# SCH_USB2MULTIRS_2022-08-20.net
KiCad netlist of a schematic drawn in EasyEDA
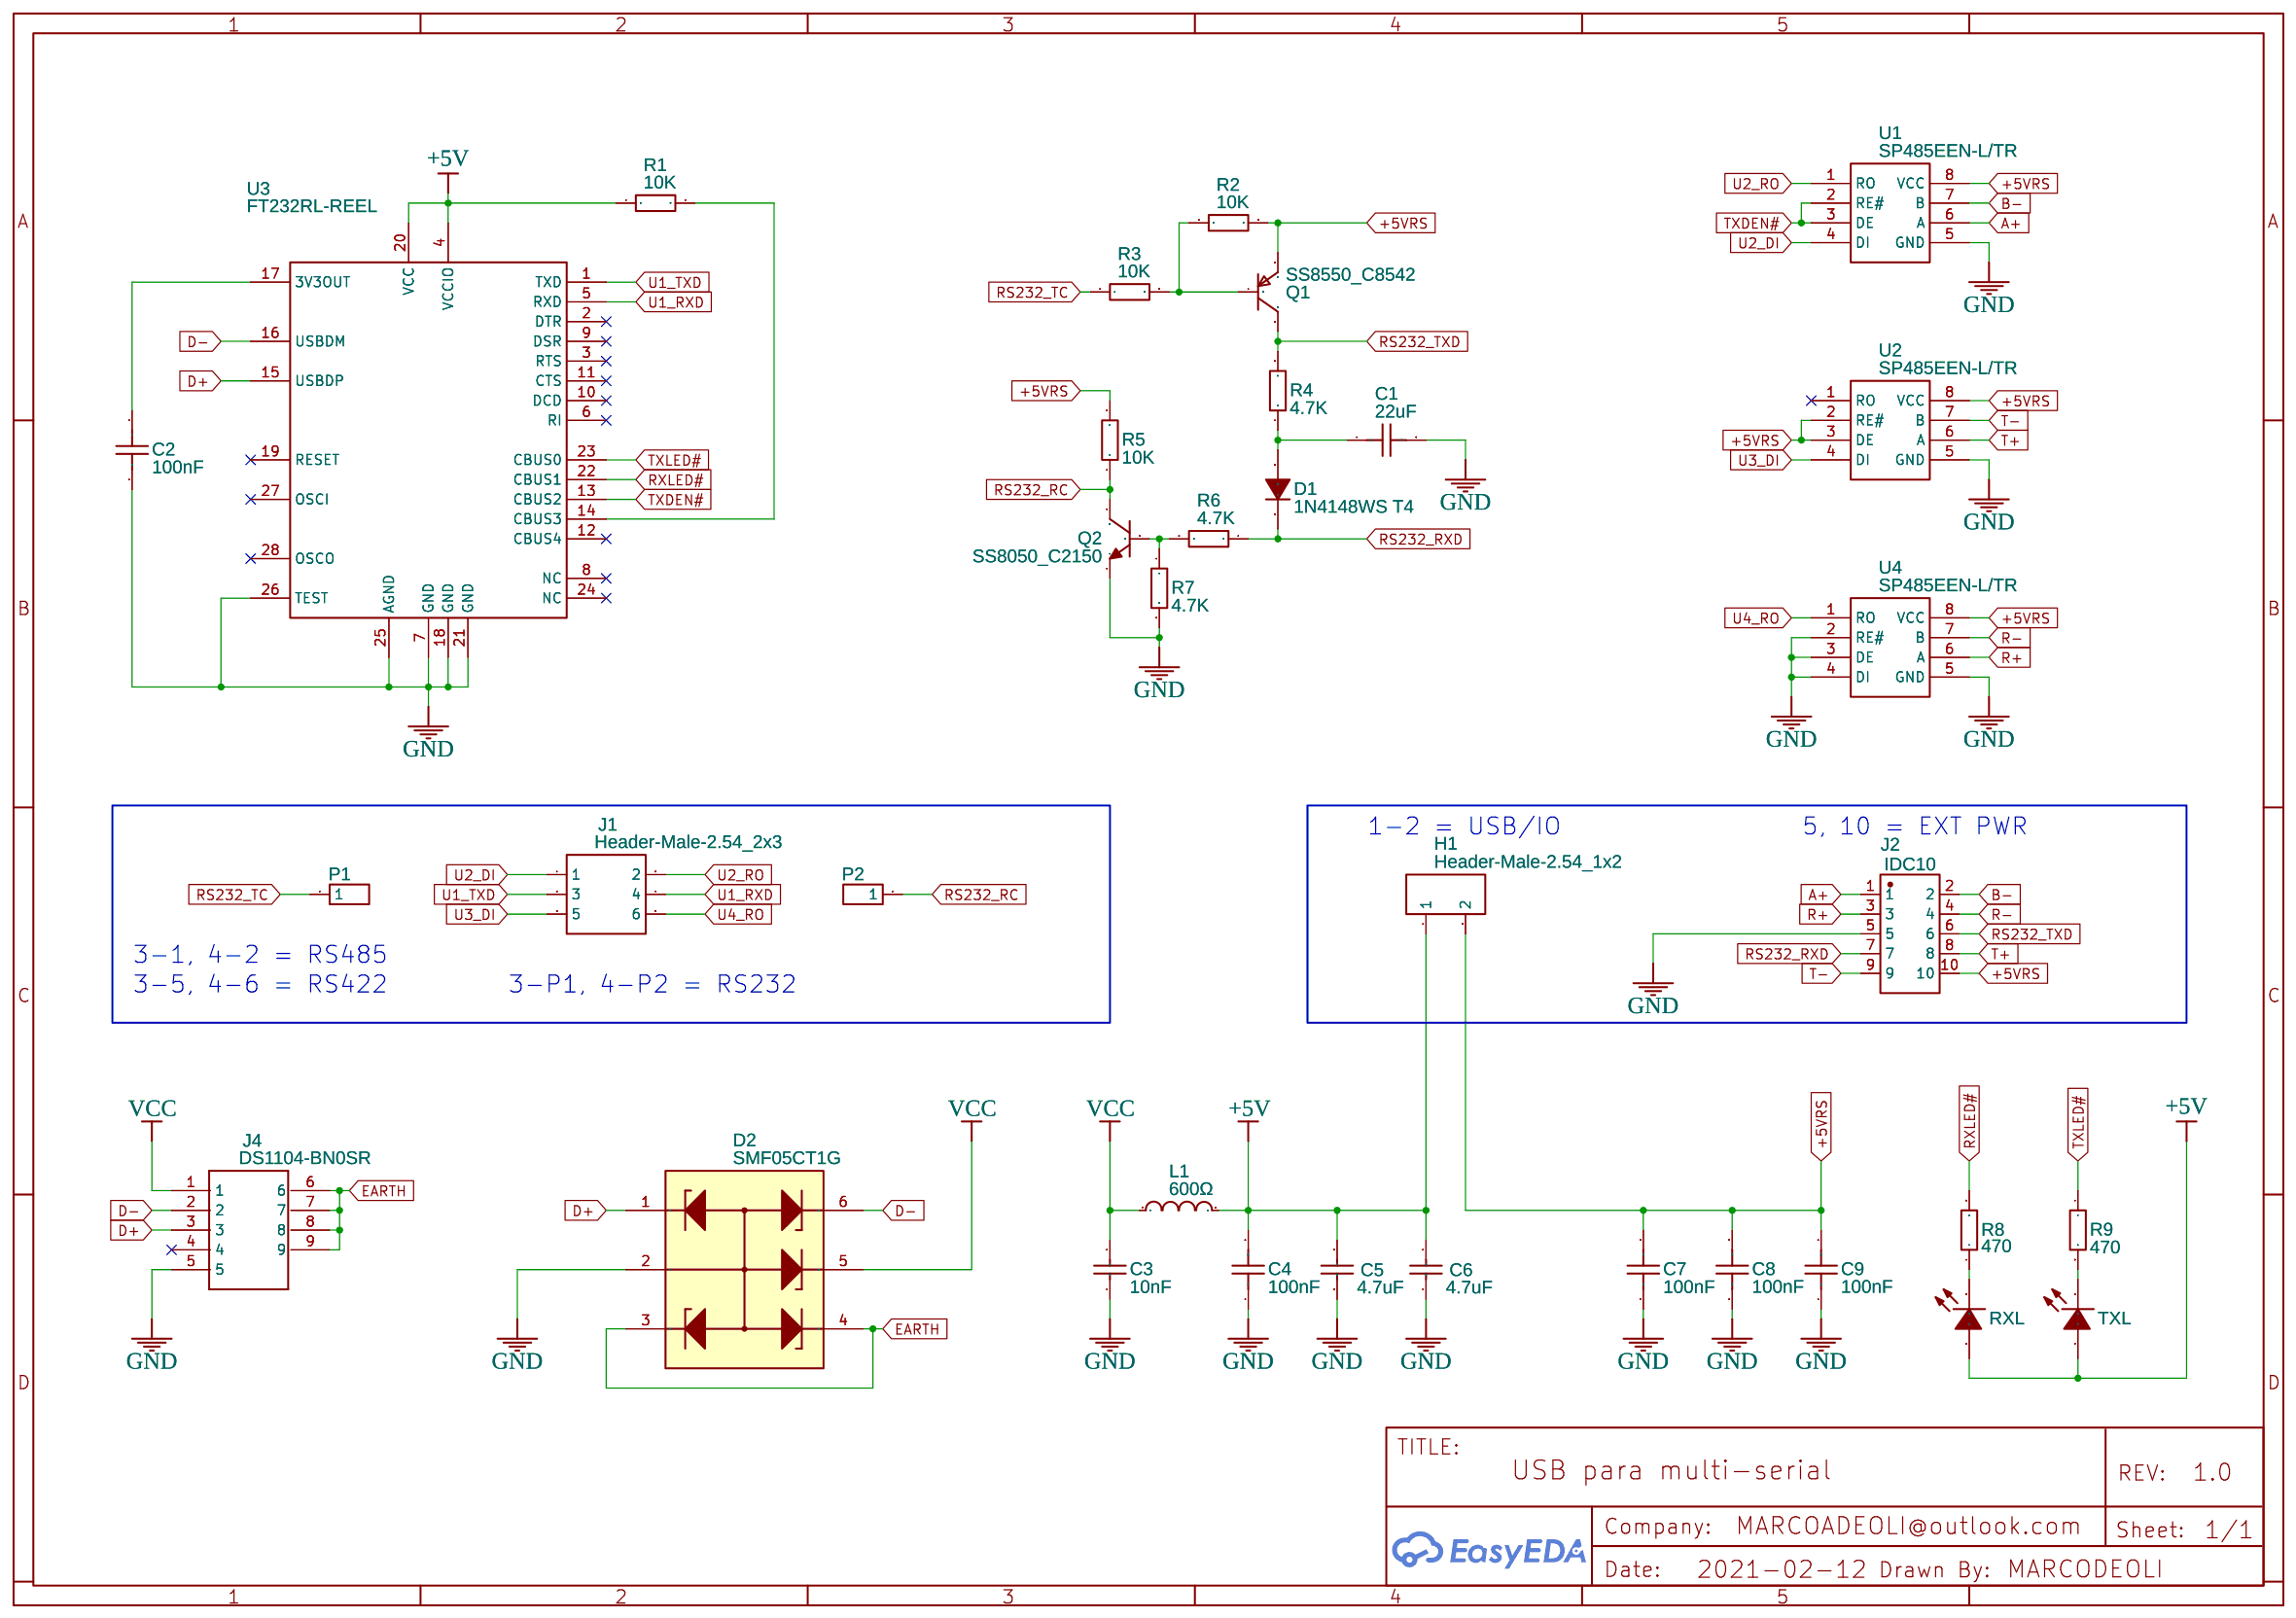
[diagram p0: schematic sheet]

(export (version "E")
  (design (tool "Eeschema 10.0.6"))
  (components
    (comp (ref "C1")
      (value "22uF")
      (fields
        (field (name "BOM_Manufacturer Part") "CL21A226MAQNNNE")
        (field (name "BOM_Supplier Part") "C45783")
      )
      (libsource (lib "") (part "CL21A226MAQNNNE"))
    )
    (comp (ref "C2")
      (value "100nF")
      (fields
        (field (name "BOM_Manufacturer Part") "CC0603KRX7R9BB104")
        (field (name "BOM_Supplier Part") "C14663")
      )
      (libsource (lib "") (part "CC0603KRX7R9BB104"))
    )
    (comp (ref "C3")
      (value "10nF")
      (fields
        (field (name "BOM_Manufacturer Part") "0603B103K500NT")
        (field (name "BOM_Supplier Part") "C57112")
      )
      (libsource (lib "") (part "0603B103K500NT"))
    )
    (comp (ref "C4")
      (value "100nF")
      (fields
        (field (name "BOM_Manufacturer Part") "CC0603KRX7R9BB104")
        (field (name "BOM_Supplier Part") "C14663")
      )
      (libsource (lib "") (part "CC0603KRX7R9BB104"))
    )
    (comp (ref "C5")
      (value "4.7uF")
      (fields
        (field (name "BOM_Manufacturer Part") "CL10A475KO8NNNC")
        (field (name "BOM_Supplier Part") "C19666")
      )
      (libsource (lib "") (part "CL10A475KO8NNNC"))
    )
    (comp (ref "C6")
      (value "4.7uF")
      (fields
        (field (name "BOM_Manufacturer Part") "CL10A475KO8NNNC")
        (field (name "BOM_Supplier Part") "C19666")
      )
      (libsource (lib "") (part "CL10A475KO8NNNC"))
    )
    (comp (ref "C7")
      (value "100nF")
      (fields
        (field (name "BOM_Manufacturer Part") "CC0603KRX7R9BB104")
        (field (name "BOM_Supplier Part") "C14663")
      )
      (libsource (lib "") (part "CC0603KRX7R9BB104"))
    )
    (comp (ref "C8")
      (value "100nF")
      (fields
        (field (name "BOM_Manufacturer Part") "CC0603KRX7R9BB104")
        (field (name "BOM_Supplier Part") "C14663")
      )
      (libsource (lib "") (part "CC0603KRX7R9BB104"))
    )
    (comp (ref "C9")
      (value "100nF")
      (fields
        (field (name "BOM_Manufacturer Part") "CC0603KRX7R9BB104")
        (field (name "BOM_Supplier Part") "C14663")
      )
      (libsource (lib "") (part "CC0603KRX7R9BB104"))
    )
    (comp (ref "D1")
      (value "1N4148WS T4")
      (fields (field (name "BOM_Supplier Part") "C2128"))
      (libsource (lib "") (part "1N4148WS T4"))
    )
    (comp (ref "D2")
      (value "SMF05CT1G")
      (fields (field (name "BOM_Supplier Part") "C15879"))
      (libsource (lib "") (part "SMF05CT1G"))
    )
    (comp (ref "H1")
      (value "Header-Male-2.54_1x2")
      (fields (field (name "BOM_Manufacturer Part") "826629-2") (field (name "BOM_Supplier Part") "C86471"))
      (libsource (lib "") (part "Header-Male-2.54_1x2"))
    )
    (comp (ref "J1")
      (value "Header-Male-2.54_2x3")
      (fields (field (name "BOM_Supplier Part") "C65114"))
      (libsource (lib "") (part "Header-Male-2.54_2x3"))
    )
    (comp (ref "J2") (value "IDC10") (libsource (lib "") (part "IDC10")))
    (comp (ref "J4") (value "DS1104-BN0SR") (libsource (lib "") (part "DS1104-BN0SR")))
    (comp (ref "L1")
      (value "600Ω")
      (fields
        (field (name "BOM_Manufacturer Part") "GZ2012D601TF")
        (field (name "BOM_Supplier Part") "C1017")
      )
      (libsource (lib "") (part "GZ2012D601TF"))
    )
    (comp (ref "P1")
      (value "Header-Male-2.54_1x1")
      (fields (field (name "BOM_Supplier Part") "C81276"))
      (libsource (lib "") (part "Header-Male-2.54_1x1"))
    )
    (comp (ref "P2")
      (value "Header-Male-2.54_1x1")
      (fields (field (name "BOM_Supplier Part") "C81276"))
      (libsource (lib "") (part "Header-Male-2.54_1x1_1"))
    )
    (comp (ref "Q1")
      (value "SS8550_C8542")
      (fields (field (name "BOM_Manufacturer Part") "SS8550") (field (name "BOM_Supplier Part") "C8542"))
      (libsource (lib "") (part "SS8550_C8542"))
    )
    (comp (ref "Q2")
      (value "SS8050_C2150")
      (fields (field (name "BOM_Manufacturer Part") "SS8050") (field (name "BOM_Supplier Part") "C2150"))
      (libsource (lib "") (part "SS8050_C2150"))
    )
    (comp (ref "R1")
      (value "10K")
      (fields
        (field (name "BOM_Manufacturer Part") "0603WAF1002T5E")
        (field (name "BOM_Supplier Part") "C25804")
      )
      (libsource (lib "") (part "0603WAF1002T5E"))
    )
    (comp (ref "R2")
      (value "10K")
      (fields
        (field (name "BOM_Manufacturer Part") "0603WAF1002T5E")
        (field (name "BOM_Supplier Part") "C25804")
      )
      (libsource (lib "") (part "0603WAF1002T5E"))
    )
    (comp (ref "R3")
      (value "10K")
      (fields
        (field (name "BOM_Manufacturer Part") "0603WAF1002T5E")
        (field (name "BOM_Supplier Part") "C25804")
      )
      (libsource (lib "") (part "0603WAF1002T5E"))
    )
    (comp (ref "R4")
      (value "4.7K")
      (fields
        (field (name "BOM_Manufacturer Part") "0603WAF4701T5E")
        (field (name "BOM_Supplier Part") "C23162")
      )
      (libsource (lib "") (part "0603WAF4701T5E_1"))
    )
    (comp (ref "R5")
      (value "10K")
      (fields
        (field (name "BOM_Manufacturer Part") "0603WAF1002T5E")
        (field (name "BOM_Supplier Part") "C25804")
      )
      (libsource (lib "") (part "0603WAF1002T5E_1"))
    )
    (comp (ref "R6")
      (value "4.7K")
      (fields
        (field (name "BOM_Manufacturer Part") "0603WAF4701T5E")
        (field (name "BOM_Supplier Part") "C23162")
      )
      (libsource (lib "") (part "0603WAF4701T5E_2"))
    )
    (comp (ref "R7")
      (value "4.7K")
      (fields
        (field (name "BOM_Manufacturer Part") "0603WAF4701T5E")
        (field (name "BOM_Supplier Part") "C23162")
      )
      (libsource (lib "") (part "0603WAF4701T5E"))
    )
    (comp (ref "R8")
      (value "470")
      (fields
        (field (name "BOM_Manufacturer Part") "0603WAF4700T5E")
        (field (name "BOM_Supplier Part") "C23179")
      )
      (libsource (lib "") (part "0603WAF4700T5E"))
    )
    (comp (ref "R9")
      (value "470")
      (fields
        (field (name "BOM_Manufacturer Part") "0603WAF4700T5E")
        (field (name "BOM_Supplier Part") "C23179")
      )
      (libsource (lib "") (part "0603WAF4700T5E_1"))
    )
    (comp (ref "RXL")
      (value "RXL")
      (fields
        (field (name "BOM_Manufacturer Part") "0603White light")
        (field (name "BOM_Supplier Part") "C2290")
      )
      (libsource (lib "") (part "0603White light_C2290"))
    )
    (comp (ref "TXL")
      (value "TXL")
      (fields (field (name "BOM_Manufacturer Part") "KT-0603R") (field (name "BOM_Supplier Part") "C2286"))
      (libsource (lib "") (part "KT-0603R"))
    )
    (comp (ref "U1")
      (value "SP485EEN-L/TR")
      (fields (field (name "BOM_Supplier Part") "C6855"))
      (libsource (lib "") (part "SP485EEN-L/TR"))
    )
    (comp (ref "U2")
      (value "SP485EEN-L/TR")
      (fields (field (name "BOM_Supplier Part") "C6855"))
      (libsource (lib "") (part "SP485EEN-L/TR"))
    )
    (comp (ref "U3")
      (value "FT232RL-REEL")
      (fields (field (name "BOM_Supplier Part") "C8690"))
      (libsource (lib "") (part "FT232RL-REEL"))
    )
    (comp (ref "U4")
      (value "SP485EEN-L/TR")
      (fields (field (name "BOM_Supplier Part") "C6855"))
      (libsource (lib "") (part "SP485EEN-L/TR"))
    )
  )
  (nets
    (net (code "1") (name "+5V") (class "Default")
      (node (ref "C4") (pin "2") (pinfunction "2_2") (pintype "unspecified"))
      (node (ref "C5") (pin "2") (pinfunction "2_2") (pintype "input"))
      (node (ref "C6") (pin "2") (pinfunction "2_2") (pintype "input"))
      (node (ref "H1") (pin "1") (pinfunction "1_1") (pintype "unspecified"))
      (node (ref "L1") (pin "2") (pinfunction "2_2") (pintype "unspecified"))
      (node (ref "R1") (pin "1") (pinfunction "1_1") (pintype "input"))
      (node (ref "RXL") (pin "1") (pinfunction "A_1") (pintype "unspecified"))
      (node (ref "TXL") (pin "1") (pinfunction "A_1") (pintype "unspecified"))
      (node (ref "U3") (pin "20") (pinfunction "VCC_20") (pintype "passive"))
      (node (ref "U3") (pin "4") (pinfunction "VCCIO_4") (pintype "passive"))
    )
    (net (code "2") (name "+5VRS") (class "Default")
      (node (ref "C7") (pin "2") (pinfunction "2_2") (pintype "unspecified"))
      (node (ref "C8") (pin "2") (pinfunction "2_2") (pintype "unspecified"))
      (node (ref "C9") (pin "2") (pinfunction "2_2") (pintype "unspecified"))
      (node (ref "H1") (pin "2") (pinfunction "2_2") (pintype "unspecified"))
      (node (ref "J2") (pin "10") (pinfunction "10_10") (pintype "unspecified"))
      (node (ref "Q1") (pin "2") (pinfunction "E_2") (pintype "unspecified"))
      (node (ref "R2") (pin "2") (pinfunction "2_2") (pintype "input"))
      (node (ref "R5") (pin "2") (pinfunction "2_2") (pintype "input"))
      (node (ref "U1") (pin "8") (pinfunction "VCC_8") (pintype "unspecified"))
      (node (ref "U2") (pin "2") (pinfunction "RE#_2") (pintype "unspecified"))
      (node (ref "U2") (pin "3") (pinfunction "DE_3") (pintype "unspecified"))
      (node (ref "U2") (pin "8") (pinfunction "VCC_8") (pintype "unspecified"))
      (node (ref "U4") (pin "8") (pinfunction "VCC_8") (pintype "unspecified"))
    )
    (net (code "3") (name "A+") (class "Default")
      (node (ref "J2") (pin "1") (pinfunction "1_1") (pintype "unspecified"))
      (node (ref "U1") (pin "6") (pinfunction "A_6") (pintype "unspecified"))
    )
    (net (code "4") (name "B-") (class "Default")
      (node (ref "J2") (pin "2") (pinfunction "2_2") (pintype "unspecified"))
      (node (ref "U1") (pin "7") (pinfunction "B_7") (pintype "unspecified"))
    )
    (net (code "5") (name "D+") (class "Default")
      (node (ref "D2") (pin "1") (pinfunction "1_1") (pintype "input"))
      (node (ref "J4") (pin "3") (pinfunction "3_3") (pintype "bidirectional"))
      (node (ref "U3") (pin "15") (pinfunction "USBDP_15") (pintype "bidirectional"))
    )
    (net (code "6") (name "D-") (class "Default")
      (node (ref "D2") (pin "6") (pinfunction "6_6") (pintype "input"))
      (node (ref "J4") (pin "2") (pinfunction "2_2") (pintype "bidirectional"))
      (node (ref "U3") (pin "16") (pinfunction "USBDM_16") (pintype "bidirectional"))
    )
    (net (code "7") (name "EARTH") (class "Default")
      (node (ref "D2") (pin "3") (pinfunction "3_3") (pintype "input"))
      (node (ref "D2") (pin "4") (pinfunction "4_4") (pintype "input"))
      (node (ref "J4") (pin "6") (pinfunction "6_6") (pintype "bidirectional"))
      (node (ref "J4") (pin "7") (pinfunction "7_7") (pintype "bidirectional"))
      (node (ref "J4") (pin "8") (pinfunction "8_8") (pintype "bidirectional"))
      (node (ref "J4") (pin "9") (pinfunction "9_9") (pintype "bidirectional"))
    )
    (net (code "8") (name "GND") (class "Default")
      (node (ref "C1") (pin "2") (pinfunction "2_2") (pintype "unspecified"))
      (node (ref "C2") (pin "1") (pinfunction "1_1") (pintype "unspecified"))
      (node (ref "C3") (pin "1") (pinfunction "1_1") (pintype "input"))
      (node (ref "C4") (pin "1") (pinfunction "1_1") (pintype "unspecified"))
      (node (ref "C5") (pin "1") (pinfunction "1_1") (pintype "input"))
      (node (ref "C6") (pin "1") (pinfunction "1_1") (pintype "input"))
      (node (ref "C7") (pin "1") (pinfunction "1_1") (pintype "unspecified"))
      (node (ref "C8") (pin "1") (pinfunction "1_1") (pintype "unspecified"))
      (node (ref "C9") (pin "1") (pinfunction "1_1") (pintype "unspecified"))
      (node (ref "D2") (pin "2") (pinfunction "2_2") (pintype "input"))
      (node (ref "J2") (pin "5") (pinfunction "5_5") (pintype "unspecified"))
      (node (ref "J4") (pin "5") (pinfunction "5_5") (pintype "bidirectional"))
      (node (ref "Q2") (pin "2") (pinfunction "E_2") (pintype "unspecified"))
      (node (ref "R7") (pin "2") (pinfunction "2_2") (pintype "input"))
      (node (ref "U1") (pin "5") (pinfunction "GND_5") (pintype "unspecified"))
      (node (ref "U2") (pin "5") (pinfunction "GND_5") (pintype "unspecified"))
      (node (ref "U3") (pin "18") (pinfunction "GND_18") (pintype "passive"))
      (node (ref "U3") (pin "21") (pinfunction "GND_21") (pintype "passive"))
      (node (ref "U3") (pin "25") (pinfunction "AGND_25") (pintype "passive"))
      (node (ref "U3") (pin "26") (pinfunction "TEST_26") (pintype "unspecified"))
      (node (ref "U3") (pin "7") (pinfunction "GND_7") (pintype "passive"))
      (node (ref "U4") (pin "2") (pinfunction "RE#_2") (pintype "unspecified"))
      (node (ref "U4") (pin "3") (pinfunction "DE_3") (pintype "unspecified"))
      (node (ref "U4") (pin "4") (pinfunction "DI_4") (pintype "unspecified"))
      (node (ref "U4") (pin "5") (pinfunction "GND_5") (pintype "unspecified"))
    )
    (net (code "9") (name "Net-(D1-A)") (class "Default")
      (node (ref "C1") (pin "1") (pinfunction "1_1") (pintype "unspecified"))
      (node (ref "D1") (pin "2") (pinfunction "A_2") (pintype "unspecified"))
      (node (ref "R4") (pin "1") (pinfunction "1_1") (pintype "input"))
    )
    (net (code "10") (name "Net-(Q1-B)") (class "Default")
      (node (ref "Q1") (pin "1") (pinfunction "B_1") (pintype "unspecified"))
      (node (ref "R2") (pin "1") (pinfunction "1_1") (pintype "input"))
      (node (ref "R3") (pin "2") (pinfunction "2_2") (pintype "input"))
    )
    (net (code "11") (name "Net-(Q2-B)") (class "Default")
      (node (ref "Q2") (pin "1") (pinfunction "B_1") (pintype "unspecified"))
      (node (ref "R6") (pin "2") (pinfunction "2_2") (pintype "input"))
      (node (ref "R7") (pin "1") (pinfunction "1_1") (pintype "input"))
    )
    (net (code "12") (name "Net-(RXL-K)") (class "Default")
      (node (ref "R8") (pin "1") (pinfunction "1_1") (pintype "input"))
      (node (ref "RXL") (pin "2") (pinfunction "K_2") (pintype "unspecified"))
    )
    (net (code "13") (name "Net-(TXL-K)") (class "Default")
      (node (ref "R9") (pin "2") (pinfunction "2_2") (pintype "input"))
      (node (ref "TXL") (pin "2") (pinfunction "K_2") (pintype "unspecified"))
    )
    (net (code "14") (name "Net-(U3-3V3OUT)") (class "Default")
      (node (ref "C2") (pin "2") (pinfunction "2_2") (pintype "unspecified"))
      (node (ref "U3") (pin "17") (pinfunction "3V3OUT_17") (pintype "output"))
    )
    (net (code "15") (name "Net-(U3-CBUS3)") (class "Default")
      (node (ref "R1") (pin "2") (pinfunction "2_2") (pintype "input"))
      (node (ref "U3") (pin "14") (pinfunction "CBUS3_14") (pintype "bidirectional"))
    )
    (net (code "16") (name "R+") (class "Default")
      (node (ref "J2") (pin "3") (pinfunction "3_3") (pintype "unspecified"))
      (node (ref "U4") (pin "6") (pinfunction "A_6") (pintype "unspecified"))
    )
    (net (code "17") (name "R-") (class "Default")
      (node (ref "J2") (pin "4") (pinfunction "4_4") (pintype "unspecified"))
      (node (ref "U4") (pin "7") (pinfunction "B_7") (pintype "unspecified"))
    )
    (net (code "18") (name "RS232_RC") (class "Default")
      (node (ref "P2") (pin "1") (pinfunction "1_1") (pintype "input"))
      (node (ref "Q2") (pin "3") (pinfunction "C_3") (pintype "unspecified"))
      (node (ref "R5") (pin "1") (pinfunction "1_1") (pintype "input"))
    )
    (net (code "19") (name "RS232_RXD") (class "Default")
      (node (ref "D1") (pin "1") (pinfunction "K_1") (pintype "unspecified"))
      (node (ref "J2") (pin "7") (pinfunction "7_7") (pintype "unspecified"))
      (node (ref "R6") (pin "1") (pinfunction "1_1") (pintype "input"))
    )
    (net (code "20") (name "RS232_TC") (class "Default")
      (node (ref "P1") (pin "1") (pinfunction "1_1") (pintype "input"))
      (node (ref "R3") (pin "1") (pinfunction "1_1") (pintype "input"))
    )
    (net (code "21") (name "RS232_TXD") (class "Default")
      (node (ref "J2") (pin "6") (pinfunction "6_6") (pintype "unspecified"))
      (node (ref "Q1") (pin "3") (pinfunction "C_3") (pintype "unspecified"))
      (node (ref "R4") (pin "2") (pinfunction "2_2") (pintype "input"))
    )
    (net (code "22") (name "RXLED#") (class "Default")
      (node (ref "R8") (pin "2") (pinfunction "2_2") (pintype "input"))
      (node (ref "U3") (pin "22") (pinfunction "CBUS1_22") (pintype "bidirectional"))
    )
    (net (code "23") (name "T+") (class "Default")
      (node (ref "J2") (pin "8") (pinfunction "8_8") (pintype "unspecified"))
      (node (ref "U2") (pin "6") (pinfunction "A_6") (pintype "unspecified"))
    )
    (net (code "24") (name "T-") (class "Default")
      (node (ref "J2") (pin "9") (pinfunction "9_9") (pintype "unspecified"))
      (node (ref "U2") (pin "7") (pinfunction "B_7") (pintype "unspecified"))
    )
    (net (code "25") (name "TXDEN#") (class "Default")
      (node (ref "U1") (pin "2") (pinfunction "RE#_2") (pintype "unspecified"))
      (node (ref "U1") (pin "3") (pinfunction "DE_3") (pintype "unspecified"))
      (node (ref "U3") (pin "13") (pinfunction "CBUS2_13") (pintype "bidirectional"))
    )
    (net (code "26") (name "TXLED#") (class "Default")
      (node (ref "R9") (pin "1") (pinfunction "1_1") (pintype "input"))
      (node (ref "U3") (pin "23") (pinfunction "CBUS0_23") (pintype "bidirectional"))
    )
    (net (code "27") (name "U1_RXD") (class "Default")
      (node (ref "J1") (pin "4") (pinfunction "4_4") (pintype "input"))
      (node (ref "U3") (pin "5") (pinfunction "RXD_5") (pintype "unspecified"))
    )
    (net (code "28") (name "U1_TXD") (class "Default")
      (node (ref "J1") (pin "3") (pinfunction "3_3") (pintype "input"))
      (node (ref "U3") (pin "1") (pinfunction "TXD_1") (pintype "output"))
    )
    (net (code "29") (name "U2_DI") (class "Default")
      (node (ref "J1") (pin "1") (pinfunction "1_1") (pintype "input"))
      (node (ref "U1") (pin "4") (pinfunction "DI_4") (pintype "unspecified"))
    )
    (net (code "30") (name "U2_RO") (class "Default")
      (node (ref "J1") (pin "2") (pinfunction "2_2") (pintype "input"))
      (node (ref "U1") (pin "1") (pinfunction "RO_1") (pintype "unspecified"))
    )
    (net (code "31") (name "U3_DI") (class "Default")
      (node (ref "J1") (pin "5") (pinfunction "5_5") (pintype "input"))
      (node (ref "U2") (pin "4") (pinfunction "DI_4") (pintype "unspecified"))
    )
    (net (code "32") (name "U4_RO") (class "Default")
      (node (ref "J1") (pin "6") (pinfunction "6_6") (pintype "input"))
      (node (ref "U4") (pin "1") (pinfunction "RO_1") (pintype "unspecified"))
    )
    (net (code "33") (name "VCC") (class "Default")
      (node (ref "C3") (pin "2") (pinfunction "2_2") (pintype "input"))
      (node (ref "D2") (pin "5") (pinfunction "5_5") (pintype "input"))
      (node (ref "J4") (pin "1") (pinfunction "1_1") (pintype "bidirectional"))
      (node (ref "L1") (pin "1") (pinfunction "1_1") (pintype "unspecified"))
    )
    (net (code "34") (name "unconnected-(J4-Pad4)") (class "Default")
      (node (ref "J4") (pin "4") (pinfunction "4_4") (pintype "bidirectional+no_connect"))
    )
    (net (code "35") (name "unconnected-(U2-RO-Pad1)") (class "Default")
      (node (ref "U2") (pin "1") (pinfunction "RO_1") (pintype "unspecified+no_connect"))
    )
    (net (code "36") (name "unconnected-(U3-CBUS4-Pad12)") (class "Default")
      (node (ref "U3") (pin "12") (pinfunction "CBUS4_12") (pintype "bidirectional+no_connect"))
    )
    (net (code "37") (name "unconnected-(U3-CTS-Pad11)") (class "Default")
      (node (ref "U3") (pin "11") (pinfunction "CTS_11") (pintype "unspecified+no_connect"))
    )
    (net (code "38") (name "unconnected-(U3-DCD-Pad10)") (class "Default")
      (node (ref "U3") (pin "10") (pinfunction "DCD_10") (pintype "unspecified+no_connect"))
    )
    (net (code "39") (name "unconnected-(U3-DSR-Pad9)") (class "Default")
      (node (ref "U3") (pin "9") (pinfunction "DSR_9") (pintype "unspecified+no_connect"))
    )
    (net (code "40") (name "unconnected-(U3-DTR-Pad2)") (class "Default")
      (node (ref "U3") (pin "2") (pinfunction "DTR_2") (pintype "output+no_connect"))
    )
    (net (code "41") (name "unconnected-(U3-NC-Pad8)") (class "Default")
      (node (ref "U3") (pin "8") (pinfunction "NC_8") (pintype "unspecified+no_connect"))
    )
    (net (code "42") (name "unconnected-(U3-NC-Pad24)") (class "Default")
      (node (ref "U3") (pin "24") (pinfunction "NC_24") (pintype "unspecified+no_connect"))
    )
    (net (code "43") (name "unconnected-(U3-OSCI-Pad27)") (class "Default")
      (node (ref "U3") (pin "27") (pinfunction "OSCI_27") (pintype "unspecified+no_connect"))
    )
    (net (code "44") (name "unconnected-(U3-OSCO-Pad28)") (class "Default")
      (node (ref "U3") (pin "28") (pinfunction "OSCO_28") (pintype "output+no_connect"))
    )
    (net (code "45") (name "unconnected-(U3-RESET-Pad19)") (class "Default")
      (node (ref "U3") (pin "19") (pinfunction "RESET_19") (pintype "unspecified+no_connect"))
    )
    (net (code "46") (name "unconnected-(U3-RI-Pad6)") (class "Default")
      (node (ref "U3") (pin "6") (pinfunction "RI_6") (pintype "unspecified+no_connect"))
    )
    (net (code "47") (name "unconnected-(U3-RTS-Pad3)") (class "Default")
      (node (ref "U3") (pin "3") (pinfunction "RTS_3") (pintype "output+no_connect"))
    )
  )
)
